# 0xD_protov1_v10.net
KiCad netlist of a schematic drawn in EAGLE
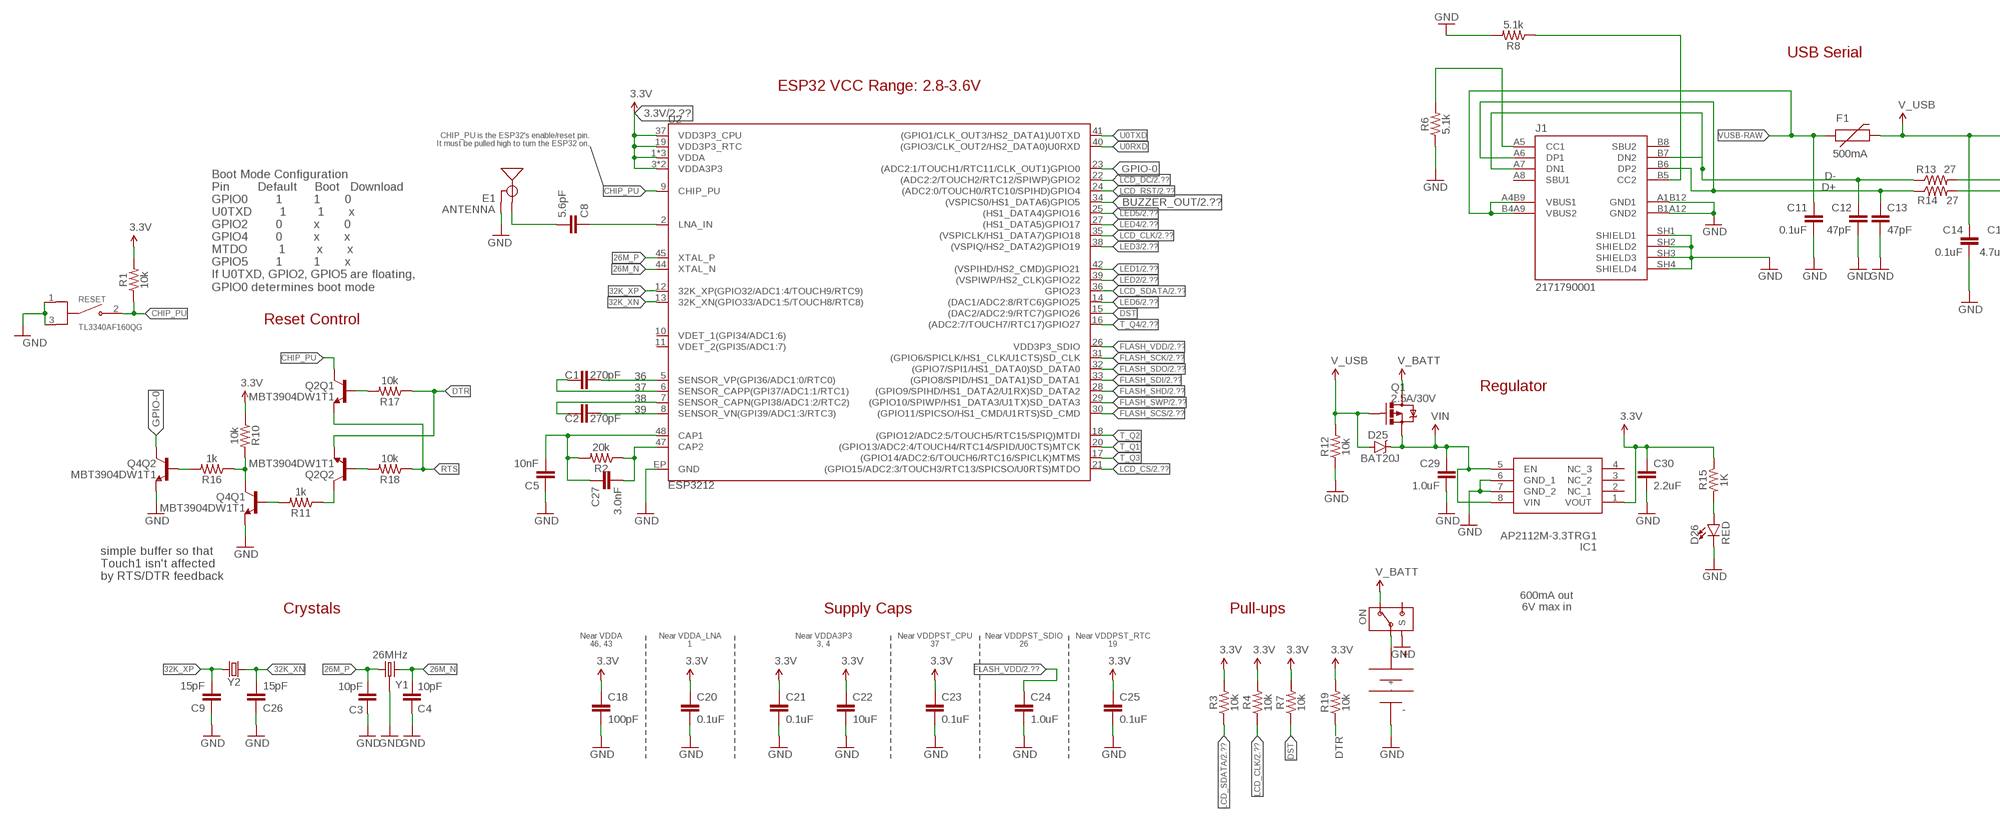
[diagram p0: schematic, sheet 1, part 1 of 2]
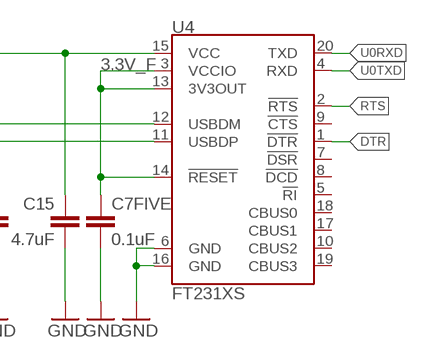
[diagram p1: schematic, sheet 1, part 2 of 2]
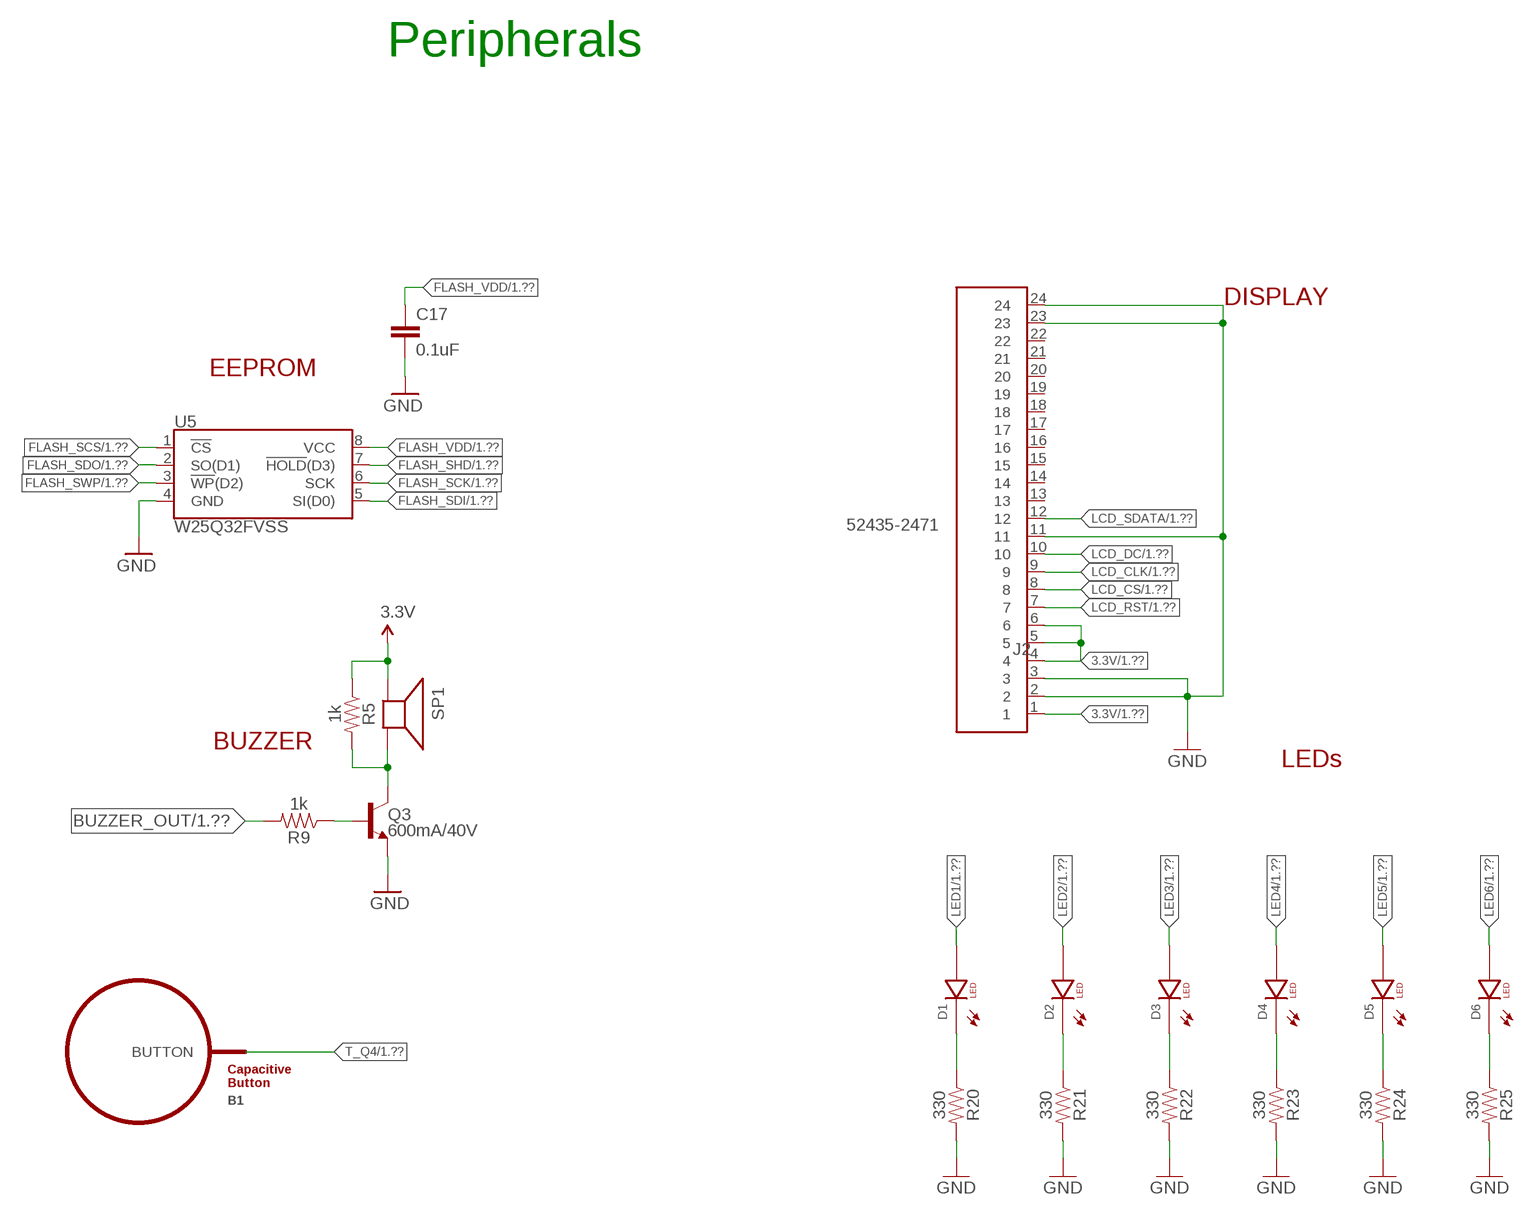
[diagram p2: schematic, sheet 2]

(export (version "E")
  (design (tool "Eeschema 10.0.6"))
  (components
    (comp (ref "C1")
      (value "270pF")
      (footprint "eagle-import:0603")
      (libsource (lib "eagle-import") (part "270PF-50V-5%(0603)"))
    )
    (comp (ref "C2")
      (value "270pF")
      (footprint "eagle-import:0603")
      (libsource (lib "eagle-import") (part "270PF-50V-5%(0603)"))
    )
    (comp (ref "C3")
      (value "10pF")
      (footprint "eagle-import:0603")
      (libsource (lib "eagle-import") (part "10PF-0603-50V-5%"))
    )
    (comp (ref "C4")
      (value "10pF")
      (footprint "eagle-import:0603")
      (libsource (lib "eagle-import") (part "10PF-0603-50V-5%"))
    )
    (comp (ref "C5")
      (value "10nF")
      (footprint "eagle-import:0603")
      (libsource (lib "eagle-import") (part "10NF-0603-50V-10%"))
    )
    (comp (ref "C7FIVE")
      (value "0.1uF")
      (footprint "eagle-import:0603")
      (libsource (lib "eagle-import") (part "0.1UF-0603-25V-(+80/-20%)"))
    )
    (comp (ref "C8")
      (value "5.6pF")
      (footprint "eagle-import:0603")
      (libsource (lib "eagle-import") (part "5.6PF-50V-5%(0603)"))
    )
    (comp (ref "C9")
      (value "15pF")
      (footprint "eagle-import:0603")
      (libsource (lib "eagle-import") (part "15PF-0603-50V-5%"))
    )
    (comp (ref "C11")
      (value "0.1uF")
      (footprint "eagle-import:0603")
      (libsource (lib "eagle-import") (part "0.1UF-0603-25V-(+80/-20%)"))
    )
    (comp (ref "C12")
      (value "47pF")
      (footprint "eagle-import:0603")
      (libsource (lib "eagle-import") (part "47PF-0603-50V-5%"))
    )
    (comp (ref "C13")
      (value "47pF")
      (footprint "eagle-import:0603")
      (libsource (lib "eagle-import") (part "47PF-0603-50V-5%"))
    )
    (comp (ref "C14")
      (value "0.1uF")
      (footprint "eagle-import:0603")
      (libsource (lib "eagle-import") (part "0.1UF-0603-25V-(+80/-20%)"))
    )
    (comp (ref "C15")
      (value "4.7uF")
      (footprint "eagle-import:0603")
      (libsource (lib "eagle-import") (part "0.1UF-0603-25V-(+80/-20%)"))
    )
    (comp (ref "C18")
      (value "100pF")
      (footprint "eagle-import:0603")
      (libsource (lib "eagle-import") (part "100PF-0603-50V-5%"))
    )
    (comp (ref "C20")
      (value "0.1uF")
      (footprint "eagle-import:0603")
      (libsource (lib "eagle-import") (part "0.1UF-0603-25V-(+80/-20%)"))
    )
    (comp (ref "C21")
      (value "0.1uF")
      (footprint "eagle-import:0603")
      (libsource (lib "eagle-import") (part "0.1UF-0603-25V-(+80/-20%)"))
    )
    (comp (ref "C22")
      (value "10uF")
      (footprint "eagle-import:0603")
      (libsource (lib "eagle-import") (part "10UF-0603-6.3V-20%"))
    )
    (comp (ref "C23")
      (value "0.1uF")
      (footprint "eagle-import:0603")
      (libsource (lib "eagle-import") (part "0.1UF-0603-25V-(+80/-20%)"))
    )
    (comp (ref "C24")
      (value "1.0uF")
      (footprint "eagle-import:0603")
      (libsource (lib "eagle-import") (part "1.0UF-0603-16V-10%"))
    )
    (comp (ref "C25")
      (value "0.1uF")
      (footprint "eagle-import:0603")
      (libsource (lib "eagle-import") (part "0.1UF-0603-25V-(+80/-20%)"))
    )
    (comp (ref "C26")
      (value "15pF")
      (footprint "eagle-import:0603")
      (libsource (lib "eagle-import") (part "15PF-0603-50V-5%"))
    )
    (comp (ref "C27")
      (value "3.0nF")
      (footprint "eagle-import:0603")
      (libsource (lib "eagle-import") (part "3.0NF-0603-50V-5%"))
    )
    (comp (ref "C29")
      (value "1.0uF")
      (footprint "eagle-import:0805")
      (libsource (lib "eagle-import") (part "1.0UF-0805-25V-(+80/-20%)"))
    )
    (comp (ref "C30")
      (value "2.2uF")
      (footprint "eagle-import:0603")
      (libsource (lib "eagle-import") (part "2.2UF-0603-10V-20%"))
    )
    (comp (ref "D25")
      (value "BAT20J")
      (footprint "eagle-import:SOD-323")
      (libsource (lib "eagle-import") (part "DIODE-SCHOTTKY-BAT20J"))
    )
    (comp (ref "D26")
      (value "RED")
      (footprint "eagle-import:LED-0603@1")
      (libsource (lib "eagle-import") (part "LED-RED0603"))
    )
    (comp (ref "E1")
      (value "ANTENNA")
      (footprint "eagle-import:TRACE_ANTENNA_2.4GHZ_25.7MM_TUNED")
      (libsource (lib "eagle-import") (part "ANTENNATRACE-TUNED"))
    )
    (comp (ref "F1")
      (value "500mA")
      (footprint "eagle-import:PTC-1206")
      (libsource (lib "eagle-import") (part "PTCSMD"))
    )
    (comp (ref "G2")
      (value "KEYSTONE_2479")
      (footprint "eagle-import:KEYSTONE_2479")
      (libsource (lib "eagle-import") (part "KEYSTONE_2479"))
    )
    (comp (ref "IC1")
      (value "AP2112M-3.3TRG1")
      (footprint "eagle-import:SOIC127P600X170-8N")
      (fields (field (name "MOUSER_PART_NUMBER") "621-AP2112M-3.3TRG1"))
      (libsource (lib "eagle-import") (part "AP2112M-3.3TRG1"))
    )
    (comp (ref "J1")
      (value "2171790001")
      (footprint "eagle-import:MOLEX_2171790001")
      (fields (field (name "MF") "Molex"))
      (libsource (lib "eagle-import") (part "2171790001"))
    )
    (comp (ref "ON")
      (value "CUS-12B")
      (footprint "eagle-import:CUS-12_SPDT")
      (libsource (lib "eagle-import") (part "CUS-12B"))
    )
    (comp (ref "Q1")
      (value "2.5A/30V")
      (footprint "eagle-import:SOT23-3@1")
      (libsource (lib "eagle-import") (part "MOSFET-PCHANNELDMG2307L"))
    )
    (comp (ref "Q2")
      (value "MBT3904DW1T1")
      (footprint "eagle-import:SC70-6")
      (libsource (lib "eagle-import") (part "MBT3904DW1T1"))
    )
    (comp (ref "Q4")
      (value "MBT3904DW1T1")
      (footprint "eagle-import:SC70-6")
      (libsource (lib "eagle-import") (part "MBT3904DW1T1"))
    )
    (comp (ref "R1")
      (value "10k")
      (footprint "eagle-import:0603")
      (libsource (lib "eagle-import") (part "10KOHM-1/10W-1%(0603)0603"))
    )
    (comp (ref "R2")
      (value "20k")
      (footprint "eagle-import:0603")
      (libsource (lib "eagle-import") (part "20KOHM-0603-1/10W-1%"))
    )
    (comp (ref "R3")
      (value "10k")
      (footprint "eagle-import:0603")
      (libsource (lib "eagle-import") (part "10KOHM-0603-1/10W-1%"))
    )
    (comp (ref "R4")
      (value "10k")
      (footprint "eagle-import:0603")
      (libsource (lib "eagle-import") (part "10KOHM-0603-1/10W-1%"))
    )
    (comp (ref "R6")
      (value "5.1k")
      (footprint "eagle-import:0603")
      (libsource (lib "eagle-import") (part "10KOHM-0603-1/10W-1%"))
    )
    (comp (ref "R7")
      (value "10k")
      (footprint "eagle-import:0603")
      (libsource (lib "eagle-import") (part "10KOHM-0603-1/10W-1%"))
    )
    (comp (ref "R8")
      (value "5.1k")
      (footprint "eagle-import:0603")
      (libsource (lib "eagle-import") (part "10KOHM-0603-1/10W-1%"))
    )
    (comp (ref "R10")
      (value "10k")
      (footprint "eagle-import:0603")
      (libsource (lib "eagle-import") (part "10KOHM-0603-1/10W-1%"))
    )
    (comp (ref "R11")
      (value "1k")
      (footprint "eagle-import:0603")
      (libsource (lib "eagle-import") (part "10KOHM-0603-1/10W-1%"))
    )
    (comp (ref "R12")
      (value "10k")
      (footprint "eagle-import:0603")
      (libsource (lib "eagle-import") (part "10KOHM-0603-1/10W-1%"))
    )
    (comp (ref "R13")
      (value "27")
      (footprint "eagle-import:0603")
      (libsource (lib "eagle-import") (part "27OHM1/10W1%(0603)0603-RES"))
    )
    (comp (ref "R14")
      (value "27")
      (footprint "eagle-import:0603")
      (libsource (lib "eagle-import") (part "27OHM1/10W1%(0603)0603-RES"))
    )
    (comp (ref "R15")
      (value "1K")
      (footprint "eagle-import:0603")
      (libsource (lib "eagle-import") (part "1KOHM-1/10W-1%(0603)"))
    )
    (comp (ref "R16")
      (value "1k")
      (footprint "eagle-import:0603")
      (libsource (lib "eagle-import") (part "10KOHM-0603-1/10W-1%"))
    )
    (comp (ref "R17")
      (value "10k")
      (footprint "eagle-import:0603")
      (libsource (lib "eagle-import") (part "10KOHM-0603-1/10W-1%"))
    )
    (comp (ref "R18")
      (value "10k")
      (footprint "eagle-import:0603")
      (libsource (lib "eagle-import") (part "10KOHM-0603-1/10W-1%"))
    )
    (comp (ref "R19")
      (value "10k")
      (footprint "eagle-import:0603")
      (libsource (lib "eagle-import") (part "10KOHM-0603-1/10W-1%"))
    )
    (comp (ref "RESET")
      (value "TL3340AF160QG")
      (footprint "eagle-import:SW_TL3340AF160QG")
      (fields (field (name "MF") "E-Switch"))
      (libsource (lib "eagle-import") (part "TL3340AF160QG"))
    )
    (comp (ref "U2")
      (value "ESP3212")
      (footprint "eagle-import:QFN48-0.4MM")
      (libsource (lib "eagle-import") (part "ESP3212"))
    )
    (comp (ref "U4")
      (value "FT231XS")
      (footprint "eagle-import:SSOP20_L")
      (libsource (lib "eagle-import") (part "FT231XS"))
    )
    (comp (ref "Y1")
      (value "26MHz")
      (footprint "eagle-import:CRYSTAL-SMD-3.2X2.5")
      (libsource (lib "eagle-import") (part "CRYSTAL-GROUNDED3.2X2.5"))
    )
    (comp (ref "Y2")
      (value "32.768kHz")
      (footprint "eagle-import:FC-12M")
      (libsource (lib "eagle-import") (part "FC-12M"))
    )
    (comp (ref "B1")
      (value "BUTTON_PASSIVE12MM")
      (footprint "eagle-import:BUTTON_PASSIVE_12MM")
      (libsource (lib "eagle-import") (part "BUTTON_PASSIVE12MM"))
    )
    (comp (ref "C17")
      (value "0.1uF")
      (footprint "eagle-import:0603")
      (libsource (lib "eagle-import") (part "0.1UF-0603-25V-(+80/-20%)"))
    )
    (comp (ref "D1")
      (value "XZDGK45WT-9-GREEN-REV")
      (footprint "eagle-import:XZ-PLCC2-REV-HOLE")
      (libsource (lib "eagle-import") (part "XZDGK45WT-9-GREEN-REV"))
    )
    (comp (ref "D2")
      (value "XZDGK45WT-9-GREEN-REV")
      (footprint "eagle-import:XZ-PLCC2-REV-HOLE")
      (libsource (lib "eagle-import") (part "XZDGK45WT-9-GREEN-REV"))
    )
    (comp (ref "D3")
      (value "XZDGK45WT-9-GREEN-REV")
      (footprint "eagle-import:XZ-PLCC2-REV-HOLE")
      (libsource (lib "eagle-import") (part "XZDGK45WT-9-GREEN-REV"))
    )
    (comp (ref "D4")
      (value "XZDGK45WT-9-GREEN-REV")
      (footprint "eagle-import:XZ-PLCC2-REV-HOLE")
      (libsource (lib "eagle-import") (part "XZDGK45WT-9-GREEN-REV"))
    )
    (comp (ref "D5")
      (value "XZDGK45WT-9-GREEN-REV")
      (footprint "eagle-import:XZ-PLCC2-REV-HOLE")
      (libsource (lib "eagle-import") (part "XZDGK45WT-9-GREEN-REV"))
    )
    (comp (ref "D6")
      (value "XZDGK45WT-9-GREEN-REV")
      (footprint "eagle-import:XZ-PLCC2-REV-HOLE")
      (libsource (lib "eagle-import") (part "XZDGK45WT-9-GREEN-REV"))
    )
    (comp (ref "J2")
      (value "52435-2471")
      (footprint "eagle-import:MOLEX_52435-2471")
      (fields (field (name "MF") "Molex"))
      (libsource (lib "eagle-import") (part "52435-2471"))
    )
    (comp (ref "Q3")
      (value "600mA/40V")
      (footprint "eagle-import:SOT23-3")
      (libsource (lib "eagle-import") (part "TRANS_NPN-MMBT2222AL"))
    )
    (comp (ref "R5")
      (value "1k")
      (footprint "eagle-import:0603")
      (libsource (lib "eagle-import") (part "10KOHM-0603-1/10W-1%"))
    )
    (comp (ref "R9")
      (value "1k")
      (footprint "eagle-import:0603")
      (libsource (lib "eagle-import") (part "10KOHM-0603-1/10W-1%"))
    )
    (comp (ref "R20")
      (value "330")
      (footprint "eagle-import:0603")
      (libsource (lib "eagle-import") (part "10KOHM-0603-1/10W-1%"))
    )
    (comp (ref "R21")
      (value "330")
      (footprint "eagle-import:0603")
      (libsource (lib "eagle-import") (part "10KOHM-0603-1/10W-1%"))
    )
    (comp (ref "R22")
      (value "330")
      (footprint "eagle-import:0603")
      (libsource (lib "eagle-import") (part "10KOHM-0603-1/10W-1%"))
    )
    (comp (ref "R23")
      (value "330")
      (footprint "eagle-import:0603")
      (libsource (lib "eagle-import") (part "10KOHM-0603-1/10W-1%"))
    )
    (comp (ref "R24")
      (value "330")
      (footprint "eagle-import:0603")
      (libsource (lib "eagle-import") (part "10KOHM-0603-1/10W-1%"))
    )
    (comp (ref "R25")
      (value "330")
      (footprint "eagle-import:0603")
      (libsource (lib "eagle-import") (part "10KOHM-0603-1/10W-1%"))
    )
    (comp (ref "SP1")
      (value "SPEAKER/PS12")
      (footprint "eagle-import:PS12")
      (libsource (lib "eagle-import") (part "SPEAKER/PS12"))
    )
    (comp (ref "U5")
      (value "W25Q32FVSS")
      (footprint "eagle-import:SOIC-8")
      (libsource (lib "eagle-import") (part "W25Q32FVSS"))
    )
  )
  (nets
    (net (code "1") (name "3.3V") (class "Default")
      (node (ref "C18") (pin "1") (pinfunction "1_1") (pintype "passive"))
      (node (ref "C20") (pin "1") (pinfunction "1_1") (pintype "passive"))
      (node (ref "C21") (pin "1") (pinfunction "1_1") (pintype "passive"))
      (node (ref "C22") (pin "1") (pinfunction "1_1") (pintype "passive"))
      (node (ref "C23") (pin "1") (pinfunction "1_1") (pintype "passive"))
      (node (ref "C25") (pin "1") (pinfunction "1_1") (pintype "passive"))
      (node (ref "C30") (pin "1") (pinfunction "1_1") (pintype "passive"))
      (node (ref "IC1") (pin "1") (pinfunction "VOUT_1") (pintype "bidirectional"))
      (node (ref "J2") (pin "1") (pinfunction "1_1") (pintype "passive"))
      (node (ref "J2") (pin "4") (pinfunction "4_4") (pintype "passive"))
      (node (ref "J2") (pin "5") (pinfunction "5_5") (pintype "passive"))
      (node (ref "J2") (pin "6") (pinfunction "6_6") (pintype "passive"))
      (node (ref "R1") (pin "2") (pinfunction "2_2") (pintype "passive"))
      (node (ref "R10") (pin "1") (pinfunction "1_1") (pintype "passive"))
      (node (ref "R15") (pin "1") (pinfunction "1_1") (pintype "passive"))
      (node (ref "R19") (pin "2") (pinfunction "2_2") (pintype "passive"))
      (node (ref "R3") (pin "2") (pinfunction "2_2") (pintype "passive"))
      (node (ref "R4") (pin "2") (pinfunction "2_2") (pintype "passive"))
      (node (ref "R5") (pin "1") (pinfunction "1_1") (pintype "passive"))
      (node (ref "R7") (pin "2") (pinfunction "2_2") (pintype "passive"))
      (node (ref "SP1") (pin "P$1") (pinfunction "+_P$1") (pintype "passive"))
      (node (ref "U2") (pin "1") (pinfunction "VDDA_1") (pintype "bidirectional"))
      (node (ref "U2") (pin "19") (pinfunction "VDD3P3_RTC_19") (pintype "bidirectional"))
      (node (ref "U2") (pin "3") (pinfunction "VDDA3P3_3") (pintype "bidirectional"))
      (node (ref "U2") (pin "37") (pinfunction "VDD3P3_CPU_37") (pintype "bidirectional"))
      (node (ref "U2") (pin "4") (pinfunction "VDDA3P3_4") (pintype "bidirectional"))
      (node (ref "U2") (pin "43") (pinfunction "VDDA_43") (pintype "bidirectional"))
      (node (ref "U2") (pin "46") (pinfunction "VDDA_46") (pintype "bidirectional"))
    )
    (net (code "2") (name "3.3V_F") (class "Default")
      (node (ref "C7FIVE") (pin "1") (pinfunction "1_1") (pintype "passive"))
      (node (ref "U4") (pin "13") (pinfunction "3V3OUT_13") (pintype "bidirectional"))
      (node (ref "U4") (pin "14") (pinfunction "~{RESET}_14") (pintype "bidirectional"))
      (node (ref "U4") (pin "3") (pinfunction "VCCIO_3") (pintype "bidirectional"))
    )
    (net (code "3") (name "26M_N") (class "Default")
      (node (ref "C4") (pin "2") (pinfunction "2_2") (pintype "passive"))
      (node (ref "U2") (pin "44") (pinfunction "XTAL_N_44") (pintype "bidirectional"))
      (node (ref "Y1") (pin "3") (pinfunction "2_3") (pintype "passive"))
    )
    (net (code "4") (name "26M_P") (class "Default")
      (node (ref "C3") (pin "2") (pinfunction "2_2") (pintype "passive"))
      (node (ref "U2") (pin "45") (pinfunction "XTAL_P_45") (pintype "bidirectional"))
      (node (ref "Y1") (pin "1") (pinfunction "1_1") (pintype "passive"))
    )
    (net (code "5") (name "32K_XN") (class "Default")
      (node (ref "C26") (pin "2") (pinfunction "2_2") (pintype "passive"))
      (node (ref "U2") (pin "13") (pinfunction "32K_XN(GPIO33/ADC1:5/TOUCH8/RTC8)_13") (pintype "bidirectional"))
      (node (ref "Y2") (pin "2") (pinfunction "2_2") (pintype "passive"))
    )
    (net (code "6") (name "32K_XP") (class "Default")
      (node (ref "C9") (pin "2") (pinfunction "2_2") (pintype "passive"))
      (node (ref "U2") (pin "12") (pinfunction "32K_XP(GPIO32/ADC1:4/TOUCH9/RTC9)_12") (pintype "bidirectional"))
      (node (ref "Y2") (pin "1") (pinfunction "1_1") (pintype "passive"))
    )
    (net (code "7") (name "36") (class "Default")
      (node (ref "C1") (pin "2") (pinfunction "2_2") (pintype "passive"))
      (node (ref "U2") (pin "5") (pinfunction "SENSOR_VP(GPI36/ADC1:0/RTC0)_5") (pintype "bidirectional"))
    )
    (net (code "8") (name "37") (class "Default")
      (node (ref "C1") (pin "1") (pinfunction "1_1") (pintype "passive"))
      (node (ref "U2") (pin "6") (pinfunction "SENSOR_CAPP(GPI37/ADC1:1/RTC1)_6") (pintype "bidirectional"))
    )
    (net (code "9") (name "38") (class "Default")
      (node (ref "C2") (pin "1") (pinfunction "1_1") (pintype "passive"))
      (node (ref "U2") (pin "7") (pinfunction "SENSOR_CAPN(GPI38/ADC1:2/RTC2)_7") (pintype "bidirectional"))
    )
    (net (code "10") (name "39") (class "Default")
      (node (ref "C2") (pin "2") (pinfunction "2_2") (pintype "passive"))
      (node (ref "U2") (pin "8") (pinfunction "SENSOR_VN(GPI39/ADC1:3/RTC3)_8") (pintype "bidirectional"))
    )
    (net (code "11") (name "BUZZER_OUT") (class "Default")
      (node (ref "R9") (pin "2") (pinfunction "2_2") (pintype "passive"))
      (node (ref "U2") (pin "34") (pinfunction "(VSPICS0/HS1_DATA6)GPIO5_34") (pintype "bidirectional"))
    )
    (net (code "12") (name "CHIP_PU") (class "Default")
      (node (ref "Q2") (pin "3") (pinfunction "C_3") (pintype "passive"))
      (node (ref "R1") (pin "1") (pinfunction "1_1") (pintype "passive"))
      (node (ref "RESET") (pin "2") (pinfunction "NO_2") (pintype "passive"))
      (node (ref "U2") (pin "9") (pinfunction "CHIP_PU_9") (pintype "bidirectional"))
    )
    (net (code "13") (name "D+") (class "Default")
      (node (ref "C13") (pin "1") (pinfunction "1_1") (pintype "passive"))
      (node (ref "J1") (pin "A6") (pinfunction "DP1_A6") (pintype "bidirectional"))
      (node (ref "J1") (pin "B6") (pinfunction "DP2_B6") (pintype "bidirectional"))
      (node (ref "R14") (pin "1") (pinfunction "1_1") (pintype "passive"))
    )
    (net (code "14") (name "D-") (class "Default")
      (node (ref "C12") (pin "1") (pinfunction "1_1") (pintype "passive"))
      (node (ref "J1") (pin "A7") (pinfunction "DN1_A7") (pintype "bidirectional"))
      (node (ref "J1") (pin "B7") (pinfunction "DN2_B7") (pintype "bidirectional"))
      (node (ref "R13") (pin "1") (pinfunction "1_1") (pintype "passive"))
    )
    (net (code "15") (name "DST") (class "Default")
      (node (ref "R7") (pin "1") (pinfunction "1_1") (pintype "passive"))
      (node (ref "U2") (pin "15") (pinfunction "(DAC2/ADC2:9/RTC7)GPIO26_15") (pintype "bidirectional"))
    )
    (net (code "16") (name "DTR") (class "Default")
      (node (ref "Q2") (pin "1") (pinfunction "E_1") (pintype "passive"))
      (node (ref "R17") (pin "1") (pinfunction "1_1") (pintype "passive"))
      (node (ref "R19") (pin "1") (pinfunction "1_1") (pintype "passive"))
      (node (ref "U4") (pin "1") (pinfunction "~{DTR}_1") (pintype "bidirectional"))
    )
    (net (code "17") (name "FLASH_SCK") (class "Default")
      (node (ref "U2") (pin "31") (pinfunction "(GPIO6/SPICLK/HS1_CLK/U1CTS)SD_CLK_31") (pintype "bidirectional"))
      (node (ref "U5") (pin "6") (pinfunction "SCK_6") (pintype "bidirectional"))
    )
    (net (code "18") (name "FLASH_SCS") (class "Default")
      (node (ref "U2") (pin "30") (pinfunction "(GPIO11/SPICSO/HS1_CMD/U1RTS)SD_CMD_30") (pintype "bidirectional"))
      (node (ref "U5") (pin "1") (pinfunction "~{CS}_1") (pintype "bidirectional"))
    )
    (net (code "19") (name "FLASH_SDI") (class "Default")
      (node (ref "U2") (pin "33") (pinfunction "(GPIO8/SPID/HS1_DATA1)SD_DATA1_33") (pintype "bidirectional"))
      (node (ref "U5") (pin "5") (pinfunction "SI(D0)_5") (pintype "bidirectional"))
    )
    (net (code "20") (name "FLASH_SDO") (class "Default")
      (node (ref "U2") (pin "32") (pinfunction "(GPIO7/SPI1/HS1_DATA0)SD_DATA0_32") (pintype "bidirectional"))
      (node (ref "U5") (pin "2") (pinfunction "SO(D1)_2") (pintype "bidirectional"))
    )
    (net (code "21") (name "FLASH_SHD") (class "Default")
      (node (ref "U2") (pin "28") (pinfunction "(GPIO9/SPIHD/HS1_DATA2/U1RX)SD_DATA2_28") (pintype "bidirectional"))
      (node (ref "U5") (pin "7") (pinfunction "~{HOLD}(D3)_7") (pintype "bidirectional"))
    )
    (net (code "22") (name "FLASH_SWP") (class "Default")
      (node (ref "U2") (pin "29") (pinfunction "(GPIO10/SPIWP/HS1_DATA3/U1TX)SD_DATA3_29") (pintype "bidirectional"))
      (node (ref "U5") (pin "3") (pinfunction "~{WP}(D2)_3") (pintype "bidirectional"))
    )
    (net (code "23") (name "FLASH_VDD") (class "Default")
      (node (ref "C17") (pin "1") (pinfunction "1_1") (pintype "passive"))
      (node (ref "C24") (pin "1") (pinfunction "1_1") (pintype "passive"))
      (node (ref "U2") (pin "26") (pinfunction "VDD3P3_SDIO_26") (pintype "bidirectional"))
      (node (ref "U5") (pin "8") (pinfunction "VCC_8") (pintype "bidirectional"))
    )
    (net (code "24") (name "GND") (class "Default")
      (node (ref "C11") (pin "2") (pinfunction "2_2") (pintype "passive"))
      (node (ref "C12") (pin "2") (pinfunction "2_2") (pintype "passive"))
      (node (ref "C13") (pin "2") (pinfunction "2_2") (pintype "passive"))
      (node (ref "C14") (pin "2") (pinfunction "2_2") (pintype "passive"))
      (node (ref "C15") (pin "2") (pinfunction "2_2") (pintype "passive"))
      (node (ref "C17") (pin "2") (pinfunction "2_2") (pintype "passive"))
      (node (ref "C18") (pin "2") (pinfunction "2_2") (pintype "passive"))
      (node (ref "C20") (pin "2") (pinfunction "2_2") (pintype "passive"))
      (node (ref "C21") (pin "2") (pinfunction "2_2") (pintype "passive"))
      (node (ref "C22") (pin "2") (pinfunction "2_2") (pintype "passive"))
      (node (ref "C23") (pin "2") (pinfunction "2_2") (pintype "passive"))
      (node (ref "C24") (pin "2") (pinfunction "2_2") (pintype "passive"))
      (node (ref "C25") (pin "2") (pinfunction "2_2") (pintype "passive"))
      (node (ref "C26") (pin "1") (pinfunction "1_1") (pintype "passive"))
      (node (ref "C29") (pin "2") (pinfunction "2_2") (pintype "passive"))
      (node (ref "C3") (pin "1") (pinfunction "1_1") (pintype "passive"))
      (node (ref "C30") (pin "2") (pinfunction "2_2") (pintype "passive"))
      (node (ref "C4") (pin "1") (pinfunction "1_1") (pintype "passive"))
      (node (ref "C5") (pin "1") (pinfunction "1_1") (pintype "passive"))
      (node (ref "C7FIVE") (pin "2") (pinfunction "2_2") (pintype "passive"))
      (node (ref "C9") (pin "1") (pinfunction "1_1") (pintype "passive"))
      (node (ref "D26") (pin "C") (pinfunction "C_C") (pintype "passive"))
      (node (ref "E1") (pin "GND") (pinfunction "GND_GND") (pintype "bidirectional"))
      (node (ref "E1") (pin "GND2") (pinfunction "GND_GND2") (pintype "bidirectional"))
      (node (ref "G2") (pin "-") (pinfunction "-_-") (pintype "bidirectional"))
      (node (ref "IC1") (pin "6") (pinfunction "GND_1_6") (pintype "bidirectional"))
      (node (ref "IC1") (pin "7") (pinfunction "GND_2_7") (pintype "bidirectional"))
      (node (ref "J1") (pin "A1B12") (pinfunction "GND1_A1B12") (pintype "power_in"))
      (node (ref "J1") (pin "B1A12") (pinfunction "GND2_B1A12") (pintype "power_in"))
      (node (ref "J1") (pin "SH1") (pinfunction "SHIELD1_SH1") (pintype "passive"))
      (node (ref "J1") (pin "SH2") (pinfunction "SHIELD2_SH2") (pintype "passive"))
      (node (ref "J1") (pin "SH3") (pinfunction "SHIELD3_SH3") (pintype "passive"))
      (node (ref "J1") (pin "SH4") (pinfunction "SHIELD4_SH4") (pintype "passive"))
      (node (ref "J2") (pin "11") (pinfunction "11_11") (pintype "passive"))
      (node (ref "J2") (pin "2") (pinfunction "2_2") (pintype "passive"))
      (node (ref "J2") (pin "23") (pinfunction "23_23") (pintype "passive"))
      (node (ref "J2") (pin "24") (pinfunction "24_24") (pintype "passive"))
      (node (ref "J2") (pin "3") (pinfunction "3_3") (pintype "passive"))
      (node (ref "ON") (pin "P$4") (pinfunction "S_P$4") (pintype "bidirectional"))
      (node (ref "ON") (pin "P$5") (pinfunction "S_P$5") (pintype "bidirectional"))
      (node (ref "ON") (pin "P$6") (pinfunction "S_P$6") (pintype "bidirectional"))
      (node (ref "ON") (pin "P$7") (pinfunction "S_P$7") (pintype "bidirectional"))
      (node (ref "Q3") (pin "2") (pinfunction "E_2") (pintype "passive"))
      (node (ref "Q4") (pin "1") (pinfunction "E_1") (pintype "passive"))
      (node (ref "Q4") (pin "4") (pinfunction "E_4") (pintype "passive"))
      (node (ref "R12") (pin "1") (pinfunction "1_1") (pintype "passive"))
      (node (ref "R20") (pin "2") (pinfunction "2_2") (pintype "passive"))
      (node (ref "R21") (pin "2") (pinfunction "2_2") (pintype "passive"))
      (node (ref "R22") (pin "2") (pinfunction "2_2") (pintype "passive"))
      (node (ref "R23") (pin "2") (pinfunction "2_2") (pintype "passive"))
      (node (ref "R24") (pin "2") (pinfunction "2_2") (pintype "passive"))
      (node (ref "R25") (pin "2") (pinfunction "2_2") (pintype "passive"))
      (node (ref "R6") (pin "1") (pinfunction "1_1") (pintype "passive"))
      (node (ref "R8") (pin "2") (pinfunction "2_2") (pintype "passive"))
      (node (ref "RESET") (pin "1") (pinfunction "COM_1_1") (pintype "passive"))
      (node (ref "RESET") (pin "3") (pinfunction "COM_2_3") (pintype "passive"))
      (node (ref "U2") (pin "EP") (pinfunction "GND_EP") (pintype "bidirectional"))
      (node (ref "U4") (pin "16") (pinfunction "GND_16") (pintype "bidirectional"))
      (node (ref "U4") (pin "6") (pinfunction "GND_6") (pintype "bidirectional"))
      (node (ref "U5") (pin "4") (pinfunction "GND_4") (pintype "bidirectional"))
      (node (ref "Y1") (pin "2") (pinfunction "GND_2") (pintype "passive"))
      (node (ref "Y1") (pin "4") (pinfunction "GND_4") (pintype "passive"))
    )
    (net (code "25") (name "GPIO-0") (class "Default")
      (node (ref "Q4") (pin "6") (pinfunction "C_6") (pintype "passive"))
      (node (ref "U2") (pin "23") (pinfunction "(ADC2:1/TOUCH1/RTC11/CLK_OUT1)GPIO0_23") (pintype "bidirectional"))
    )
    (net (code "26") (name "LCD_CLK") (class "Default")
      (node (ref "J2") (pin "9") (pinfunction "9_9") (pintype "passive"))
      (node (ref "R4") (pin "1") (pinfunction "1_1") (pintype "passive"))
      (node (ref "U2") (pin "35") (pinfunction "(VSPICLK/HS1_DATA7)GPIO18_35") (pintype "bidirectional"))
    )
    (net (code "27") (name "LCD_CS") (class "Default")
      (node (ref "J2") (pin "8") (pinfunction "8_8") (pintype "passive"))
      (node (ref "U2") (pin "21") (pinfunction "(GPIO15/ADC2:3/TOUCH3/RTC13/SPICSO/U0RTS)MTDO_21") (pintype "bidirectional"))
    )
    (net (code "28") (name "LCD_DC") (class "Default")
      (node (ref "J2") (pin "10") (pinfunction "10_10") (pintype "passive"))
      (node (ref "U2") (pin "22") (pinfunction "(ADC2:2/TOUCH2/RTC12/SPIWP)GPIO2_22") (pintype "bidirectional"))
    )
    (net (code "29") (name "LCD_RST") (class "Default")
      (node (ref "J2") (pin "7") (pinfunction "7_7") (pintype "passive"))
      (node (ref "U2") (pin "24") (pinfunction "(ADC2:0/TOUCH0/RTC10/SPIHD)GPIO4_24") (pintype "bidirectional"))
    )
    (net (code "30") (name "LCD_SDATA") (class "Default")
      (node (ref "J2") (pin "12") (pinfunction "12_12") (pintype "passive"))
      (node (ref "R3") (pin "1") (pinfunction "1_1") (pintype "passive"))
      (node (ref "U2") (pin "36") (pinfunction "GPIO23_36") (pintype "bidirectional"))
    )
    (net (code "31") (name "LED1") (class "Default")
      (node (ref "D1") (pin "ANODE") (pinfunction "ANODE_ANODE") (pintype "bidirectional"))
      (node (ref "U2") (pin "42") (pinfunction "(VSPIHD/HS2_CMD)GPIO21_42") (pintype "bidirectional"))
    )
    (net (code "32") (name "LED2") (class "Default")
      (node (ref "D2") (pin "ANODE") (pinfunction "ANODE_ANODE") (pintype "bidirectional"))
      (node (ref "U2") (pin "39") (pinfunction "(VSPIWP/HS2_CLK)GPIO22_39") (pintype "bidirectional"))
    )
    (net (code "33") (name "LED3") (class "Default")
      (node (ref "D3") (pin "ANODE") (pinfunction "ANODE_ANODE") (pintype "bidirectional"))
      (node (ref "U2") (pin "38") (pinfunction "(VSPIQ/HS2_DATA2)GPIO19_38") (pintype "bidirectional"))
    )
    (net (code "34") (name "LED4") (class "Default")
      (node (ref "D4") (pin "ANODE") (pinfunction "ANODE_ANODE") (pintype "bidirectional"))
      (node (ref "U2") (pin "27") (pinfunction "(HS1_DATA5)GPIO17_27") (pintype "bidirectional"))
    )
    (net (code "35") (name "LED5") (class "Default")
      (node (ref "D5") (pin "ANODE") (pinfunction "ANODE_ANODE") (pintype "bidirectional"))
      (node (ref "U2") (pin "25") (pinfunction "(HS1_DATA4)GPIO16_25") (pintype "bidirectional"))
    )
    (net (code "36") (name "LED6") (class "Default")
      (node (ref "D6") (pin "ANODE") (pinfunction "ANODE_ANODE") (pintype "bidirectional"))
      (node (ref "U2") (pin "14") (pinfunction "(DAC1/ADC2:8/RTC6)GPIO25_14") (pintype "bidirectional"))
    )
    (net (code "37") (name "Net-(D1-PadCATHODE)") (class "Default")
      (node (ref "D1") (pin "CATHODE") (pinfunction "CATHODE_CATHODE") (pintype "bidirectional"))
      (node (ref "R20") (pin "1") (pinfunction "1_1") (pintype "passive"))
    )
    (net (code "38") (name "Net-(D2-PadCATHODE)") (class "Default")
      (node (ref "D2") (pin "CATHODE") (pinfunction "CATHODE_CATHODE") (pintype "bidirectional"))
      (node (ref "R21") (pin "1") (pinfunction "1_1") (pintype "passive"))
    )
    (net (code "39") (name "Net-(D3-PadCATHODE)") (class "Default")
      (node (ref "D3") (pin "CATHODE") (pinfunction "CATHODE_CATHODE") (pintype "bidirectional"))
      (node (ref "R22") (pin "1") (pinfunction "1_1") (pintype "passive"))
    )
    (net (code "40") (name "Net-(D4-PadCATHODE)") (class "Default")
      (node (ref "D4") (pin "CATHODE") (pinfunction "CATHODE_CATHODE") (pintype "bidirectional"))
      (node (ref "R23") (pin "1") (pinfunction "1_1") (pintype "passive"))
    )
    (net (code "41") (name "Net-(D5-PadCATHODE)") (class "Default")
      (node (ref "D5") (pin "CATHODE") (pinfunction "CATHODE_CATHODE") (pintype "bidirectional"))
      (node (ref "R24") (pin "1") (pinfunction "1_1") (pintype "passive"))
    )
    (net (code "42") (name "Net-(D6-PadCATHODE)") (class "Default")
      (node (ref "D6") (pin "CATHODE") (pinfunction "CATHODE_CATHODE") (pintype "bidirectional"))
      (node (ref "R25") (pin "1") (pinfunction "1_1") (pintype "passive"))
    )
    (net (code "43") (name "Net-(D26-PadA)") (class "Default")
      (node (ref "D26") (pin "A") (pinfunction "A_A") (pintype "passive"))
      (node (ref "R15") (pin "2") (pinfunction "2_2") (pintype "passive"))
    )
    (net (code "44") (name "Net-(E1-SIGNAL)") (class "Default")
      (node (ref "C8") (pin "2") (pinfunction "2_2") (pintype "passive"))
      (node (ref "E1") (pin "ANT") (pinfunction "SIGNAL_ANT") (pintype "bidirectional"))
    )
    (net (code "45") (name "Net-(J1-CC1)") (class "Default")
      (node (ref "J1") (pin "A5") (pinfunction "CC1_A5") (pintype "bidirectional"))
      (node (ref "R6") (pin "2") (pinfunction "2_2") (pintype "passive"))
    )
    (net (code "46") (name "Net-(J1-CC2)") (class "Default")
      (node (ref "J1") (pin "B5") (pinfunction "CC2_B5") (pintype "bidirectional"))
      (node (ref "R8") (pin "1") (pinfunction "1_1") (pintype "passive"))
    )
    (net (code "47") (name "Net-(ON-1)") (class "Default")
      (node (ref "G2") (pin "+") (pinfunction "+_+") (pintype "bidirectional"))
      (node (ref "ON") (pin "P$2") (pinfunction "1_P$2") (pintype "bidirectional"))
    )
    (net (code "48") (name "Net-(Q2A-B)") (class "Default")
      (node (ref "Q2") (pin "5") (pinfunction "B_5") (pintype "passive"))
      (node (ref "R17") (pin "2") (pinfunction "2_2") (pintype "passive"))
    )
    (net (code "49") (name "Net-(Q2B-B)") (class "Default")
      (node (ref "Q2") (pin "2") (pinfunction "B_2") (pintype "passive"))
      (node (ref "R18") (pin "2") (pinfunction "2_2") (pintype "passive"))
    )
    (net (code "50") (name "Net-(Q2B-C)") (class "Default")
      (node (ref "Q2") (pin "6") (pinfunction "C_6") (pintype "passive"))
      (node (ref "R11") (pin "1") (pinfunction "1_1") (pintype "passive"))
    )
    (net (code "51") (name "Net-(Q3-B)") (class "Default")
      (node (ref "Q3") (pin "1") (pinfunction "B_1") (pintype "passive"))
      (node (ref "R9") (pin "1") (pinfunction "1_1") (pintype "passive"))
    )
    (net (code "52") (name "Net-(Q3-C)") (class "Default")
      (node (ref "Q3") (pin "3") (pinfunction "C_3") (pintype "passive"))
      (node (ref "R5") (pin "2") (pinfunction "2_2") (pintype "passive"))
      (node (ref "SP1") (pin "P$2") (pinfunction "-_P$2") (pintype "passive"))
    )
    (net (code "53") (name "Net-(Q4A-B)") (class "Default")
      (node (ref "Q4") (pin "5") (pinfunction "B_5") (pintype "passive"))
      (node (ref "R11") (pin "2") (pinfunction "2_2") (pintype "passive"))
    )
    (net (code "54") (name "Net-(Q4A-C)") (class "Default")
      (node (ref "Q4") (pin "3") (pinfunction "C_3") (pintype "passive"))
      (node (ref "R10") (pin "2") (pinfunction "2_2") (pintype "passive"))
      (node (ref "R16") (pin "1") (pinfunction "1_1") (pintype "passive"))
    )
    (net (code "55") (name "Net-(Q4B-B)") (class "Default")
      (node (ref "Q4") (pin "2") (pinfunction "B_2") (pintype "passive"))
      (node (ref "R16") (pin "2") (pinfunction "2_2") (pintype "passive"))
    )
    (net (code "56") (name "Net-(U2-CAP1)") (class "Default")
      (node (ref "C27") (pin "1") (pinfunction "1_1") (pintype "passive"))
      (node (ref "C5") (pin "2") (pinfunction "2_2") (pintype "passive"))
      (node (ref "R2") (pin "2") (pinfunction "2_2") (pintype "passive"))
      (node (ref "U2") (pin "48") (pinfunction "CAP1_48") (pintype "bidirectional"))
    )
    (net (code "57") (name "Net-(U2-CAP2)") (class "Default")
      (node (ref "C27") (pin "2") (pinfunction "2_2") (pintype "passive"))
      (node (ref "R2") (pin "1") (pinfunction "1_1") (pintype "passive"))
      (node (ref "U2") (pin "47") (pinfunction "CAP2_47") (pintype "bidirectional"))
    )
    (net (code "58") (name "Net-(U2-LNA_IN)") (class "Default")
      (node (ref "C8") (pin "1") (pinfunction "1_1") (pintype "passive"))
      (node (ref "U2") (pin "2") (pinfunction "LNA_IN_2") (pintype "bidirectional"))
    )
    (net (code "59") (name "Net-(U4-USBDM)") (class "Default")
      (node (ref "R13") (pin "2") (pinfunction "2_2") (pintype "passive"))
      (node (ref "U4") (pin "12") (pinfunction "USBDM_12") (pintype "bidirectional"))
    )
    (net (code "60") (name "Net-(U4-USBDP)") (class "Default")
      (node (ref "R14") (pin "2") (pinfunction "2_2") (pintype "passive"))
      (node (ref "U4") (pin "11") (pinfunction "USBDP_11") (pintype "bidirectional"))
    )
    (net (code "61") (name "RTS") (class "Default")
      (node (ref "Q2") (pin "4") (pinfunction "E_4") (pintype "passive"))
      (node (ref "R18") (pin "1") (pinfunction "1_1") (pintype "passive"))
      (node (ref "U4") (pin "2") (pinfunction "~{RTS}_2") (pintype "bidirectional"))
    )
    (net (code "62") (name "T_Q1") (class "Default")
      (node (ref "U2") (pin "20") (pinfunction "(GPIO13/ADC2:4/TOUCH4/RTC14/SPID/U0CTS)MTCK_20") (pintype "bidirectional"))
    )
    (net (code "63") (name "T_Q2") (class "Default")
      (node (ref "U2") (pin "18") (pinfunction "(GPIO12/ADC2:5/TOUCH5/RTC15/SPIQ)MTDI_18") (pintype "bidirectional"))
    )
    (net (code "64") (name "T_Q3") (class "Default")
      (node (ref "U2") (pin "17") (pinfunction "(GPIO14/ADC2:6/TOUCH6/RTC16/SPICLK)MTMS_17") (pintype "bidirectional"))
    )
    (net (code "65") (name "T_Q4") (class "Default")
      (node (ref "B1") (pin "BUTTON") (pinfunction "BUTTON_BUTTON") (pintype "passive"))
      (node (ref "U2") (pin "16") (pinfunction "(ADC2:7/TOUCH7/RTC17)GPIO27_16") (pintype "bidirectional"))
    )
    (net (code "66") (name "U0RXD") (class "Default")
      (node (ref "U2") (pin "40") (pinfunction "(GPIO3/CLK_OUT2/HS2_DATA0)U0RXD_40") (pintype "bidirectional"))
      (node (ref "U4") (pin "20") (pinfunction "TXD_20") (pintype "bidirectional"))
    )
    (net (code "67") (name "U0TXD") (class "Default")
      (node (ref "U2") (pin "41") (pinfunction "(GPIO1/CLK_OUT3/HS2_DATA1)U0TXD_41") (pintype "bidirectional"))
      (node (ref "U4") (pin "4") (pinfunction "RXD_4") (pintype "bidirectional"))
    )
    (net (code "68") (name "VIN") (class "Default")
      (node (ref "C29") (pin "1") (pinfunction "1_1") (pintype "passive"))
      (node (ref "D25") (pin "C") (pinfunction "C_C") (pintype "passive"))
      (node (ref "IC1") (pin "5") (pinfunction "EN_5") (pintype "bidirectional"))
      (node (ref "IC1") (pin "8") (pinfunction "VIN_8") (pintype "bidirectional"))
      (node (ref "Q1") (pin "2") (pinfunction "S_2") (pintype "passive"))
    )
    (net (code "69") (name "VUSB-RAW") (class "Default")
      (node (ref "C11") (pin "1") (pinfunction "1_1") (pintype "passive"))
      (node (ref "F1") (pin "1") (pinfunction "1_1") (pintype "bidirectional"))
      (node (ref "J1") (pin "A4B9") (pinfunction "VBUS1_A4B9") (pintype "power_in"))
      (node (ref "J1") (pin "B4A9") (pinfunction "VBUS2_B4A9") (pintype "power_in"))
    )
    (net (code "70") (name "V_BATT") (class "Default")
      (node (ref "ON") (pin "P$1") (pinfunction "2_P$1") (pintype "bidirectional"))
      (node (ref "Q1") (pin "3") (pinfunction "D_3") (pintype "passive"))
    )
    (net (code "71") (name "V_USB") (class "Default")
      (node (ref "C14") (pin "1") (pinfunction "1_1") (pintype "passive"))
      (node (ref "C15") (pin "1") (pinfunction "1_1") (pintype "passive"))
      (node (ref "D25") (pin "A") (pinfunction "A_A") (pintype "passive"))
      (node (ref "F1") (pin "2") (pinfunction "2_2") (pintype "bidirectional"))
      (node (ref "Q1") (pin "1") (pinfunction "G_1") (pintype "passive"))
      (node (ref "R12") (pin "2") (pinfunction "2_2") (pintype "passive"))
      (node (ref "U4") (pin "15") (pinfunction "VCC_15") (pintype "bidirectional"))
    )
    (net (code "72") (name "unconnected-(IC1-NC_1-Pad2)") (class "Default")
      (node (ref "IC1") (pin "2") (pinfunction "NC_1_2") (pintype "bidirectional"))
    )
    (net (code "73") (name "unconnected-(IC1-NC_2-Pad3)") (class "Default")
      (node (ref "IC1") (pin "3") (pinfunction "NC_2_3") (pintype "bidirectional"))
    )
    (net (code "74") (name "unconnected-(IC1-NC_3-Pad4)") (class "Default")
      (node (ref "IC1") (pin "4") (pinfunction "NC_3_4") (pintype "bidirectional"))
    )
    (net (code "75") (name "unconnected-(J1-SBU1-PadA8)") (class "Default")
      (node (ref "J1") (pin "A8") (pinfunction "SBU1_A8") (pintype "bidirectional"))
    )
    (net (code "76") (name "unconnected-(J1-SBU2-PadB8)") (class "Default")
      (node (ref "J1") (pin "B8") (pinfunction "SBU2_B8") (pintype "bidirectional"))
    )
    (net (code "77") (name "unconnected-(J2-Pad13)") (class "Default")
      (node (ref "J2") (pin "13") (pinfunction "13_13") (pintype "passive"))
    )
    (net (code "78") (name "unconnected-(J2-Pad14)") (class "Default")
      (node (ref "J2") (pin "14") (pinfunction "14_14") (pintype "passive"))
    )
    (net (code "79") (name "unconnected-(J2-Pad15)") (class "Default")
      (node (ref "J2") (pin "15") (pinfunction "15_15") (pintype "passive"))
    )
    (net (code "80") (name "unconnected-(J2-Pad16)") (class "Default")
      (node (ref "J2") (pin "16") (pinfunction "16_16") (pintype "passive"))
    )
    (net (code "81") (name "unconnected-(J2-Pad17)") (class "Default")
      (node (ref "J2") (pin "17") (pinfunction "17_17") (pintype "passive"))
    )
    (net (code "82") (name "unconnected-(J2-Pad18)") (class "Default")
      (node (ref "J2") (pin "18") (pinfunction "18_18") (pintype "passive"))
    )
    (net (code "83") (name "unconnected-(J2-Pad19)") (class "Default")
      (node (ref "J2") (pin "19") (pinfunction "19_19") (pintype "passive"))
    )
    (net (code "84") (name "unconnected-(J2-Pad20)") (class "Default")
      (node (ref "J2") (pin "20") (pinfunction "20_20") (pintype "passive"))
    )
    (net (code "85") (name "unconnected-(J2-Pad21)") (class "Default")
      (node (ref "J2") (pin "21") (pinfunction "21_21") (pintype "passive"))
    )
    (net (code "86") (name "unconnected-(J2-Pad22)") (class "Default")
      (node (ref "J2") (pin "22") (pinfunction "22_22") (pintype "passive"))
    )
    (net (code "87") (name "unconnected-(ON-3-PadP$3)") (class "Default")
      (node (ref "ON") (pin "P$3") (pinfunction "3_P$3") (pintype "bidirectional"))
    )
    (net (code "88") (name "unconnected-(U2-VDET_1(GPI34{slash}ADC1:6)-Pad10)") (class "Default")
      (node (ref "U2") (pin "10") (pinfunction "VDET_1(GPI34/ADC1:6)_10") (pintype "bidirectional"))
    )
    (net (code "89") (name "unconnected-(U2-VDET_2(GPI35{slash}ADC1:7)-Pad11)") (class "Default")
      (node (ref "U2") (pin "11") (pinfunction "VDET_2(GPI35/ADC1:7)_11") (pintype "bidirectional"))
    )
    (net (code "90") (name "unconnected-(U4-CBUS0-Pad18)") (class "Default")
      (node (ref "U4") (pin "18") (pinfunction "CBUS0_18") (pintype "bidirectional"))
    )
    (net (code "91") (name "unconnected-(U4-CBUS1-Pad17)") (class "Default")
      (node (ref "U4") (pin "17") (pinfunction "CBUS1_17") (pintype "bidirectional"))
    )
    (net (code "92") (name "unconnected-(U4-CBUS2-Pad10)") (class "Default")
      (node (ref "U4") (pin "10") (pinfunction "CBUS2_10") (pintype "bidirectional"))
    )
    (net (code "93") (name "unconnected-(U4-CBUS3-Pad19)") (class "Default")
      (node (ref "U4") (pin "19") (pinfunction "CBUS3_19") (pintype "bidirectional"))
    )
    (net (code "94") (name "unconnected-(U4-~{CTS}-Pad9)") (class "Default")
      (node (ref "U4") (pin "9") (pinfunction "~{CTS}_9") (pintype "bidirectional"))
    )
    (net (code "95") (name "unconnected-(U4-~{DCD}-Pad8)") (class "Default")
      (node (ref "U4") (pin "8") (pinfunction "~{DCD}_8") (pintype "bidirectional"))
    )
    (net (code "96") (name "unconnected-(U4-~{DSR}-Pad7)") (class "Default")
      (node (ref "U4") (pin "7") (pinfunction "~{DSR}_7") (pintype "bidirectional"))
    )
    (net (code "97") (name "unconnected-(U4-~{RI}-Pad5)") (class "Default")
      (node (ref "U4") (pin "5") (pinfunction "~{RI}_5") (pintype "bidirectional"))
    )
  )
)
